# ZOWI_Main_Board.net
KiCad netlist of a schematic drawn in Altium Designer
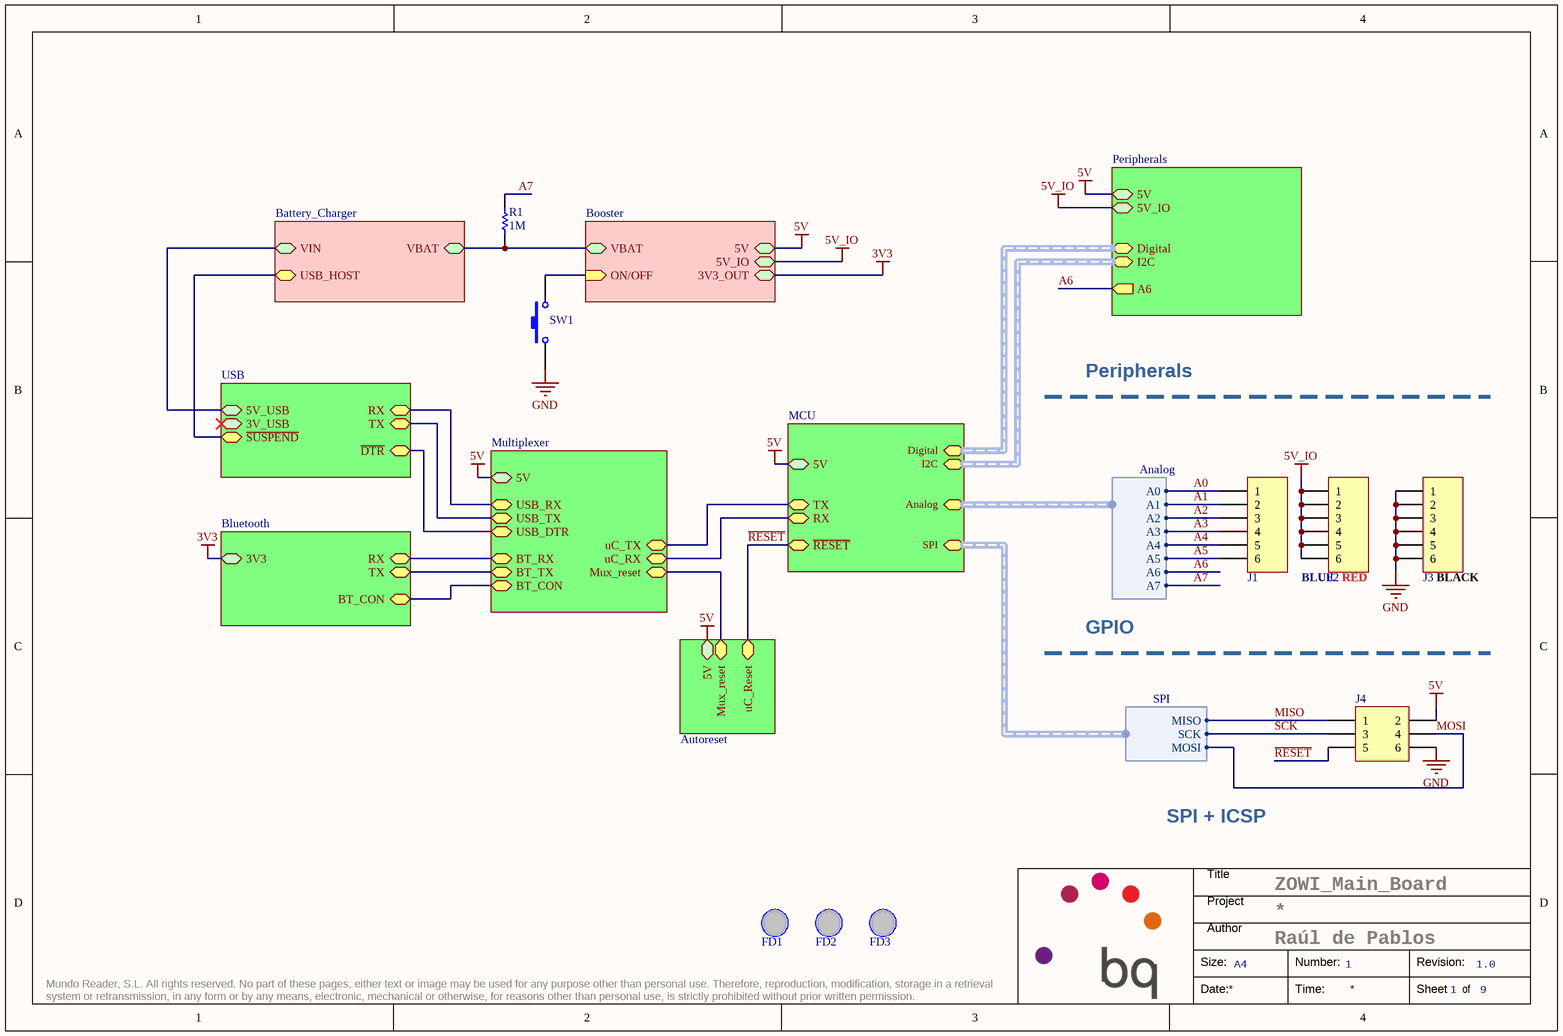
[diagram p0: ZOWI_Main_Board.SchDoc]

(export (version "E")
  (design (tool "Eeschema 10.0.6"))
  (components
    (comp (ref "FD1")
      (value "Fiducial")
      (footprint "Fiducial_1mm")
      (description "Fiducial Mark")
      (fields (field (name "PART NUMBER") "Fiducial 1mm"))
      (libsource (lib "Miscelanea") (part "Fiducial"))
    )
    (comp (ref "FD2")
      (value "Fiducial")
      (footprint "Fiducial_1mm")
      (description "Fiducial Mark")
      (fields (field (name "PART NUMBER") "Fiducial 1mm"))
      (libsource (lib "Miscelanea") (part "Fiducial"))
    )
    (comp (ref "FD3")
      (value "Fiducial")
      (footprint "Fiducial_1mm")
      (description "Fiducial Mark")
      (fields (field (name "PART NUMBER") "Fiducial 1mm"))
      (libsource (lib "Miscelanea") (part "Fiducial"))
    )
    (comp (ref "J1")
      (value "1x6 pin Header 2.54mm")
      (footprint "1x6 Pin Header 2.54")
      (description "Connector, 1x6 pin Header 2.54mm")
      (fields (field (name "MANUFACTURER") "Samtec") (field (name "PART NUMBER") "CON_PH_THT2.54_6 Blue"))
      (libsource (lib "Conectores_PinHeader_2.54") (part "1x6 pin Header 2.54mm"))
    )
    (comp (ref "J2")
      (value "1x6 pin Header 2.54mm")
      (footprint "1x6 Pin Header 2.54")
      (description "Connector, 1x6 pin Header 2.54mm")
      (fields (field (name "MANUFACTURER") "Samtec") (field (name "PART NUMBER") "CON_PH_THT2.54_6 Red"))
      (libsource (lib "Conectores_PinHeader_2.54") (part "1x6 pin Header 2.54mm"))
    )
    (comp (ref "J3")
      (value "1x6 pin Header 2.54mm")
      (footprint "1x6 Pin Header 2.54")
      (description "Connector, 1x6 pin Header 2.54mm")
      (fields (field (name "MANUFACTURER") "Samtec") (field (name "PART NUMBER") "CON_PH_THT2.54_6"))
      (libsource (lib "Conectores_PinHeader_2.54") (part "1x6 pin Header 2.54mm"))
    )
    (comp (ref "J4")
      (value "2x3 pin Header 2.54mm")
      (footprint "2x3 Pin Header 2.54")
      (description "Connector, 6 pin Dual Header 2.54mm")
      (fields (field (name "MANUFACTURER") "Samtec") (field (name "PART NUMBER") "CON_DPH_THT2.54_6"))
      (libsource (lib "Conectores_PinHeader_2.54") (part "2x3 pin Header 2.54mm"))
    )
    (comp (ref "R1")
      (value "Resistor")
      (footprint "R0402")
      (description "Resistor, SMD")
      (fields
        (field (name "TOLERANCE") "±5%")
        (field (name "POWER") "0.063W")
        (field (name "RESISTANCE") "1M")
      )
      (libsource (lib "Pasives_Resistor_SMD") (part "Resistor"))
    )
    (comp (ref "SW1")
      (value "Switch")
      (footprint "MJTP1105T")
      (description "Micro miniature pushbutton surface Switch")
      (fields (field (name "PART NUMBER") "MJTP1105T") (field (name "MANUFACTURER") "APEM"))
      (libsource (lib "Electromechanical") (part "Switch"))
    )
  )
  (nets
    (net (code "5") (name "/A0") (class "Default")
      (node (ref "J1") (pin "1") (pinfunction "1_1") (pintype "passive"))
    )
    (net (code "6") (name "/A1") (class "Default")
      (node (ref "J1") (pin "2") (pinfunction "2_2") (pintype "passive"))
    )
    (net (code "7") (name "/A2") (class "Default")
      (node (ref "J1") (pin "3") (pinfunction "3_3") (pintype "passive"))
    )
    (net (code "8") (name "/A3") (class "Default")
      (node (ref "J1") (pin "4") (pinfunction "4_4") (pintype "passive"))
    )
    (net (code "9") (name "/A4") (class "Default")
      (node (ref "J1") (pin "5") (pinfunction "5_5") (pintype "passive"))
    )
    (net (code "10") (name "/A5") (class "Default")
      (node (ref "J1") (pin "6") (pinfunction "6_6") (pintype "passive"))
    )
    (net (code "12") (name "/A7") (class "Default")
      (node (ref "R1") (pin "1") (pinfunction "1_1") (pintype "passive"))
    )
    (net (code "18") (name "/MISO") (class "Default")
      (node (ref "J4") (pin "1") (pinfunction "1_1") (pintype "passive"))
    )
    (net (code "19") (name "/MOSI") (class "Default")
      (node (ref "J4") (pin "4") (pinfunction "4_4") (pintype "passive"))
    )
    (net (code "21") (name "/ON{slash}OFF") (class "Default")
      (node (ref "SW1") (pin "2") (pinfunction "2_2") (pintype "passive"))
    )
    (net (code "24") (name "/SCK") (class "Default")
      (node (ref "J4") (pin "3") (pinfunction "3_3") (pintype "passive"))
    )
    (net (code "29") (name "/VBAT") (class "Default")
      (node (ref "R1") (pin "2") (pinfunction "2_2") (pintype "passive"))
    )
    (net (code "32") (name "/~{RESET}") (class "Default")
      (node (ref "J4") (pin "5") (pinfunction "5_5") (pintype "passive"))
    )
    (net (code "34") (name "5V") (class "Default")
      (node (ref "J4") (pin "2") (pinfunction "2_2") (pintype "passive"))
    )
    (net (code "35") (name "5V_IO") (class "Default")
      (node (ref "J2") (pin "1") (pinfunction "1_1") (pintype "passive"))
      (node (ref "J2") (pin "2") (pinfunction "2_2") (pintype "passive"))
      (node (ref "J2") (pin "3") (pinfunction "3_3") (pintype "passive"))
      (node (ref "J2") (pin "4") (pinfunction "4_4") (pintype "passive"))
      (node (ref "J2") (pin "5") (pinfunction "5_5") (pintype "passive"))
      (node (ref "J2") (pin "6") (pinfunction "6_6") (pintype "passive"))
    )
    (net (code "36") (name "GND") (class "Default")
      (node (ref "J3") (pin "1") (pinfunction "1_1") (pintype "passive"))
      (node (ref "J3") (pin "2") (pinfunction "2_2") (pintype "passive"))
      (node (ref "J3") (pin "3") (pinfunction "3_3") (pintype "passive"))
      (node (ref "J3") (pin "4") (pinfunction "4_4") (pintype "passive"))
      (node (ref "J3") (pin "5") (pinfunction "5_5") (pintype "passive"))
      (node (ref "J3") (pin "6") (pinfunction "6_6") (pintype "passive"))
      (node (ref "J4") (pin "6") (pinfunction "6_6") (pintype "passive"))
      (node (ref "SW1") (pin "1") (pinfunction "1_1") (pintype "passive"))
    )
  )
)
